# ColorNodeV1_1.net
KiCad netlist of a schematic drawn in EAGLE
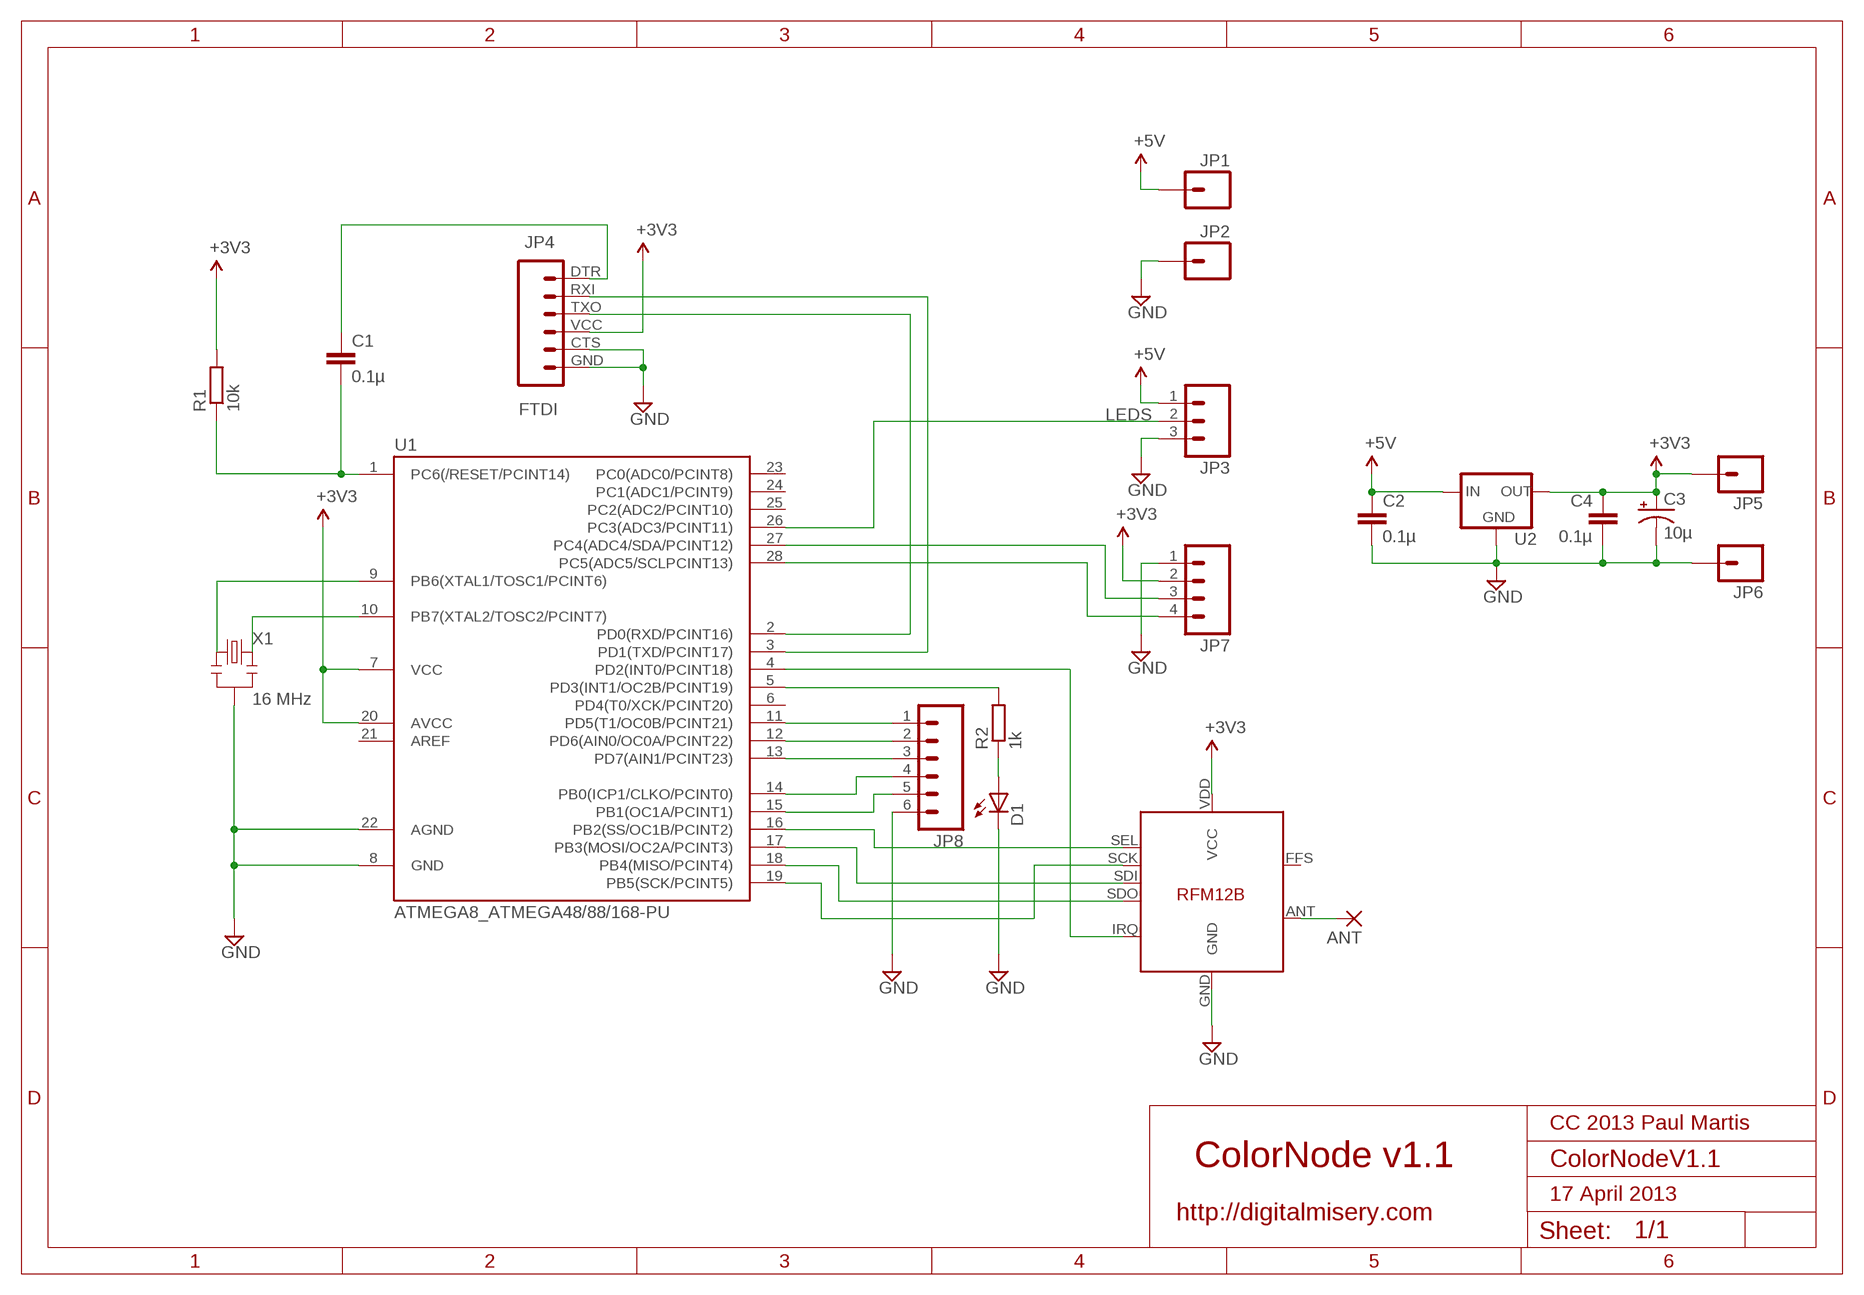
[diagram p0: schematic, sheet 1]

(export (version "E")
  (design (tool "Eeschema 10.0.6"))
  (components
    (comp (ref "ANT")
      (value "1,6/0,8")
      (footprint "eagle-import:1,6_0,8")
      (libsource (lib "eagle-import") (part "1,6/0,8"))
    )
    (comp (ref "C1")
      (value "0.1µ")
      (footprint "eagle-import:C025-024X044")
      (libsource (lib "eagle-import") (part "C-EU025-024X044"))
    )
    (comp (ref "C2")
      (value "0.1µ")
      (footprint "eagle-import:C025-024X044")
      (libsource (lib "eagle-import") (part "C-EU025-024X044"))
    )
    (comp (ref "C3")
      (value "10µ")
      (footprint "eagle-import:E1,8-4")
      (libsource (lib "eagle-import") (part "CPOL-USE1.8-4"))
    )
    (comp (ref "C4")
      (value "0.1µ")
      (footprint "eagle-import:C025-024X044")
      (libsource (lib "eagle-import") (part "C-EU025-024X044"))
    )
    (comp (ref "D1")
      (value "LED3MM")
      (footprint "eagle-import:LED3MM")
      (libsource (lib "eagle-import") (part "LED3MM"))
    )
    (comp (ref "JP1")
      (value "M01PTH_2MM")
      (footprint "eagle-import:1X01_2MM")
      (libsource (lib "eagle-import") (part "M01PTH_2MM"))
    )
    (comp (ref "JP2")
      (value "M01PTH_2MM")
      (footprint "eagle-import:1X01_2MM")
      (libsource (lib "eagle-import") (part "M01PTH_2MM"))
    )
    (comp (ref "JP3")
      (value "M031X03_NO_SILK")
      (footprint "eagle-import:1X03_NO_SILK")
      (libsource (lib "eagle-import") (part "M031X03_NO_SILK"))
    )
    (comp (ref "JP4")
      (value "FTDI")
      (footprint "eagle-import:FTDI_BASIC")
      (libsource (lib "eagle-import") (part "FTDI_BASICPTH"))
    )
    (comp (ref "JP5")
      (value "M01PTH")
      (footprint "eagle-import:1X01")
      (libsource (lib "eagle-import") (part "SparkFun-Connectors_M01PTH"))
    )
    (comp (ref "JP6")
      (value "M01PTH")
      (footprint "eagle-import:1X01")
      (libsource (lib "eagle-import") (part "SparkFun-Connectors_M01PTH"))
    )
    (comp (ref "JP7")
      (value "M041X04_NO_SILK")
      (footprint "eagle-import:1X04_NO_SILK")
      (libsource (lib "eagle-import") (part "M041X04_NO_SILK"))
    )
    (comp (ref "JP8")
      (value "M06SIP")
      (footprint "eagle-import:1X06")
      (libsource (lib "eagle-import") (part "M06SIP"))
    )
    (comp (ref "R1")
      (value "10k")
      (footprint "eagle-import:0204_7")
      (libsource (lib "eagle-import") (part "R-EU_0204/7"))
    )
    (comp (ref "R2")
      (value "1k")
      (footprint "eagle-import:0204_7")
      (libsource (lib "eagle-import") (part "R-EU_0204/7"))
    )
    (comp (ref "U1")
      (value "ATMEGA8_ATMEGA48/88/168-PU")
      (footprint "eagle-import:ATMEGA8_DIL28-3")
      (libsource (lib "eagle-import") (part "ATMEGA8_ATMEGA48/88/168-PU"))
    )
    (comp (ref "U2")
      (value "MCP1700INLINE")
      (footprint "eagle-import:TO92-INLINE")
      (libsource (lib "eagle-import") (part "MCP1700INLINE"))
    )
    (comp (ref "U3")
      (value "RFM12B")
      (footprint "eagle-import:RFM12B")
      (libsource (lib "eagle-import") (part "RFM12B"))
    )
    (comp (ref "X1")
      (value "16 MHz")
      (footprint "eagle-import:RESONATOR-PTH")
      (libsource (lib "eagle-import") (part "RESONATORPTH"))
    )
  )
  (nets
    (net (code "1") (name "+3V3") (class "Default")
      (node (ref "C3") (pin "+") (pinfunction "+_+") (pintype "passive"))
      (node (ref "C4") (pin "1") (pinfunction "1_1") (pintype "passive"))
      (node (ref "JP4") (pin "VCC") (pinfunction "4_VCC") (pintype "passive"))
      (node (ref "JP5") (pin "1") (pinfunction "1_1") (pintype "passive"))
      (node (ref "JP7") (pin "2") (pinfunction "2_2") (pintype "passive"))
      (node (ref "R1") (pin "2") (pinfunction "2_2") (pintype "passive"))
      (node (ref "U1") (pin "20") (pinfunction "AVCC_20") (pintype "passive"))
      (node (ref "U1") (pin "7") (pinfunction "VCC_7") (pintype "power_in"))
      (node (ref "U2") (pin "3") (pinfunction "OUT_3") (pintype "passive"))
      (node (ref "U3") (pin "VDD") (pinfunction "VCC_VDD") (pintype "power_in"))
    )
    (net (code "2") (name "+5V") (class "Default")
      (node (ref "C2") (pin "1") (pinfunction "1_1") (pintype "passive"))
      (node (ref "JP1") (pin "1") (pinfunction "1_1") (pintype "passive"))
      (node (ref "JP3") (pin "1") (pinfunction "1_1") (pintype "passive"))
      (node (ref "U2") (pin "2") (pinfunction "IN_2") (pintype "input"))
    )
    (net (code "3") (name "/LEDS") (class "Default")
      (node (ref "JP3") (pin "2") (pinfunction "2_2") (pintype "passive"))
      (node (ref "U1") (pin "26") (pinfunction "PC3(ADC3/PCINT11)_26") (pintype "bidirectional"))
    )
    (net (code "4") (name "GND") (class "Default")
      (node (ref "C2") (pin "2") (pinfunction "2_2") (pintype "passive"))
      (node (ref "C3") (pin "-") (pinfunction "-_-") (pintype "passive"))
      (node (ref "C4") (pin "2") (pinfunction "2_2") (pintype "passive"))
      (node (ref "D1") (pin "K") (pinfunction "C_K") (pintype "passive"))
      (node (ref "JP2") (pin "1") (pinfunction "1_1") (pintype "passive"))
      (node (ref "JP3") (pin "3") (pinfunction "3_3") (pintype "passive"))
      (node (ref "JP4") (pin "CTS") (pinfunction "5_CTS") (pintype "passive"))
      (node (ref "JP4") (pin "GND") (pinfunction "6_GND") (pintype "passive"))
      (node (ref "JP6") (pin "1") (pinfunction "1_1") (pintype "passive"))
      (node (ref "JP7") (pin "1") (pinfunction "1_1") (pintype "passive"))
      (node (ref "JP8") (pin "6") (pinfunction "6_6") (pintype "passive"))
      (node (ref "U1") (pin "22") (pinfunction "AGND_22") (pintype "power_in"))
      (node (ref "U1") (pin "8") (pinfunction "GND_8") (pintype "power_in"))
      (node (ref "U2") (pin "1") (pinfunction "GND_1") (pintype "input"))
      (node (ref "U3") (pin "GND") (pinfunction "GND_GND") (pintype "power_in"))
      (node (ref "X1") (pin "2") (pinfunction "2_2") (pintype "passive"))
    )
    (net (code "5") (name "Net-(ANT-P)") (class "Default")
      (node (ref "ANT") (pin "1") (pinfunction "P_1") (pintype "passive"))
      (node (ref "U3") (pin "ANT") (pinfunction "ANT_ANT") (pintype "passive"))
    )
    (net (code "6") (name "Net-(D1-PadA)") (class "Default")
      (node (ref "D1") (pin "A") (pinfunction "A_A") (pintype "passive"))
      (node (ref "R2") (pin "1") (pinfunction "1_1") (pintype "passive"))
    )
    (net (code "7") (name "Net-(JP4-1)") (class "Default")
      (node (ref "C1") (pin "1") (pinfunction "1_1") (pintype "passive"))
      (node (ref "JP4") (pin "DTR") (pinfunction "1_DTR") (pintype "passive"))
    )
    (net (code "8") (name "Net-(JP4-2)") (class "Default")
      (node (ref "JP4") (pin "RXI") (pinfunction "2_RXI") (pintype "passive"))
      (node (ref "U1") (pin "3") (pinfunction "PD1(TXD/PCINT17)_3") (pintype "bidirectional"))
    )
    (net (code "9") (name "Net-(JP4-3)") (class "Default")
      (node (ref "JP4") (pin "TXO") (pinfunction "3_TXO") (pintype "passive"))
      (node (ref "U1") (pin "2") (pinfunction "PD0(RXD/PCINT16)_2") (pintype "bidirectional"))
    )
    (net (code "10") (name "Net-(U1-PB0(ICP1{slash}CLKO{slash}PCINT0))") (class "Default")
      (node (ref "JP8") (pin "4") (pinfunction "4_4") (pintype "passive"))
      (node (ref "U1") (pin "14") (pinfunction "PB0(ICP1/CLKO/PCINT0)_14") (pintype "bidirectional"))
    )
    (net (code "11") (name "Net-(U1-PB1(OC1A{slash}PCINT1))") (class "Default")
      (node (ref "JP8") (pin "5") (pinfunction "5_5") (pintype "passive"))
      (node (ref "U1") (pin "15") (pinfunction "PB1(OC1A/PCINT1)_15") (pintype "bidirectional"))
    )
    (net (code "12") (name "Net-(U1-PB2(SS{slash}OC1B{slash}PCINT2))") (class "Default")
      (node (ref "U1") (pin "16") (pinfunction "PB2(SS/OC1B/PCINT2)_16") (pintype "bidirectional"))
      (node (ref "U3") (pin "SEL") (pinfunction "SEL_SEL") (pintype "input"))
    )
    (net (code "13") (name "Net-(U1-PB3(MOSI{slash}OC2A{slash}PCINT3))") (class "Default")
      (node (ref "U1") (pin "17") (pinfunction "PB3(MOSI/OC2A/PCINT3)_17") (pintype "bidirectional"))
      (node (ref "U3") (pin "SDI") (pinfunction "SDI_SDI") (pintype "input"))
    )
    (net (code "14") (name "Net-(U1-PB4(MISO{slash}PCINT4))") (class "Default")
      (node (ref "U1") (pin "18") (pinfunction "PB4(MISO/PCINT4)_18") (pintype "bidirectional"))
      (node (ref "U3") (pin "SDO") (pinfunction "SDO_SDO") (pintype "output"))
    )
    (net (code "15") (name "Net-(U1-PB5(SCK{slash}PCINT5))") (class "Default")
      (node (ref "U1") (pin "19") (pinfunction "PB5(SCK/PCINT5)_19") (pintype "bidirectional"))
      (node (ref "U3") (pin "SCK") (pinfunction "SCK_SCK") (pintype "input"))
    )
    (net (code "16") (name "Net-(U1-PB6(XTAL1{slash}TOSC1{slash}PCINT6))") (class "Default")
      (node (ref "U1") (pin "9") (pinfunction "PB6(XTAL1/TOSC1/PCINT6)_9") (pintype "bidirectional"))
      (node (ref "X1") (pin "1") (pinfunction "1_1") (pintype "passive"))
    )
    (net (code "17") (name "Net-(U1-PB7(XTAL2{slash}TOSC2{slash}PCINT7))") (class "Default")
      (node (ref "U1") (pin "10") (pinfunction "PB7(XTAL2/TOSC2/PCINT7)_10") (pintype "bidirectional"))
      (node (ref "X1") (pin "3") (pinfunction "3_3") (pintype "passive"))
    )
    (net (code "18") (name "Net-(U1-PC4(ADC4{slash}SDA{slash}PCINT12))") (class "Default")
      (node (ref "JP7") (pin "3") (pinfunction "3_3") (pintype "passive"))
      (node (ref "U1") (pin "27") (pinfunction "PC4(ADC4/SDA/PCINT12)_27") (pintype "bidirectional"))
    )
    (net (code "19") (name "Net-(U1-PC5(ADC5{slash}SCLPCINT13))") (class "Default")
      (node (ref "JP7") (pin "4") (pinfunction "4_4") (pintype "passive"))
      (node (ref "U1") (pin "28") (pinfunction "PC5(ADC5/SCLPCINT13)_28") (pintype "bidirectional"))
    )
    (net (code "20") (name "Net-(U1-PC6({slash}RESET{slash}PCINT14))") (class "Default")
      (node (ref "C1") (pin "2") (pinfunction "2_2") (pintype "passive"))
      (node (ref "R1") (pin "1") (pinfunction "1_1") (pintype "passive"))
      (node (ref "U1") (pin "1") (pinfunction "PC6(/RESET/PCINT14)_1") (pintype "bidirectional"))
    )
    (net (code "21") (name "Net-(U1-PD2(INT0{slash}PCINT18))") (class "Default")
      (node (ref "U1") (pin "4") (pinfunction "PD2(INT0/PCINT18)_4") (pintype "bidirectional"))
      (node (ref "U3") (pin "IRQ") (pinfunction "IRQ_IRQ") (pintype "open_collector"))
    )
    (net (code "22") (name "Net-(U1-PD3(INT1{slash}OC2B{slash}PCINT19))") (class "Default")
      (node (ref "R2") (pin "2") (pinfunction "2_2") (pintype "passive"))
      (node (ref "U1") (pin "5") (pinfunction "PD3(INT1/OC2B/PCINT19)_5") (pintype "bidirectional"))
    )
    (net (code "23") (name "Net-(U1-PD5(T1{slash}OC0B{slash}PCINT21))") (class "Default")
      (node (ref "JP8") (pin "1") (pinfunction "1_1") (pintype "passive"))
      (node (ref "U1") (pin "11") (pinfunction "PD5(T1/OC0B/PCINT21)_11") (pintype "bidirectional"))
    )
    (net (code "24") (name "Net-(U1-PD6(AIN0{slash}OC0A{slash}PCINT22))") (class "Default")
      (node (ref "JP8") (pin "2") (pinfunction "2_2") (pintype "passive"))
      (node (ref "U1") (pin "12") (pinfunction "PD6(AIN0/OC0A/PCINT22)_12") (pintype "bidirectional"))
    )
    (net (code "25") (name "Net-(U1-PD7(AIN1{slash}PCINT23))") (class "Default")
      (node (ref "JP8") (pin "3") (pinfunction "3_3") (pintype "passive"))
      (node (ref "U1") (pin "13") (pinfunction "PD7(AIN1/PCINT23)_13") (pintype "bidirectional"))
    )
    (net (code "26") (name "unconnected-(U1-AREF-Pad21)") (class "Default")
      (node (ref "U1") (pin "21") (pinfunction "AREF_21") (pintype "passive"))
    )
    (net (code "27") (name "unconnected-(U1-PC0(ADC0{slash}PCINT8)-Pad23)") (class "Default")
      (node (ref "U1") (pin "23") (pinfunction "PC0(ADC0/PCINT8)_23") (pintype "bidirectional"))
    )
    (net (code "28") (name "unconnected-(U1-PC1(ADC1{slash}PCINT9)-Pad24)") (class "Default")
      (node (ref "U1") (pin "24") (pinfunction "PC1(ADC1/PCINT9)_24") (pintype "bidirectional"))
    )
    (net (code "29") (name "unconnected-(U1-PC2(ADC2{slash}PCINT10)-Pad25)") (class "Default")
      (node (ref "U1") (pin "25") (pinfunction "PC2(ADC2/PCINT10)_25") (pintype "bidirectional"))
    )
    (net (code "30") (name "unconnected-(U1-PD4(T0{slash}XCK{slash}PCINT20)-Pad6)") (class "Default")
      (node (ref "U1") (pin "6") (pinfunction "PD4(T0/XCK/PCINT20)_6") (pintype "bidirectional"))
    )
    (net (code "31") (name "unconnected-(U3-PadFFS)") (class "Default")
      (node (ref "U3") (pin "FFS") (pinfunction "FFS_FFS") (pintype "bidirectional"))
    )
  )
)
